# ext_pcb.net
KiCad netlist of a schematic drawn in EAGLE
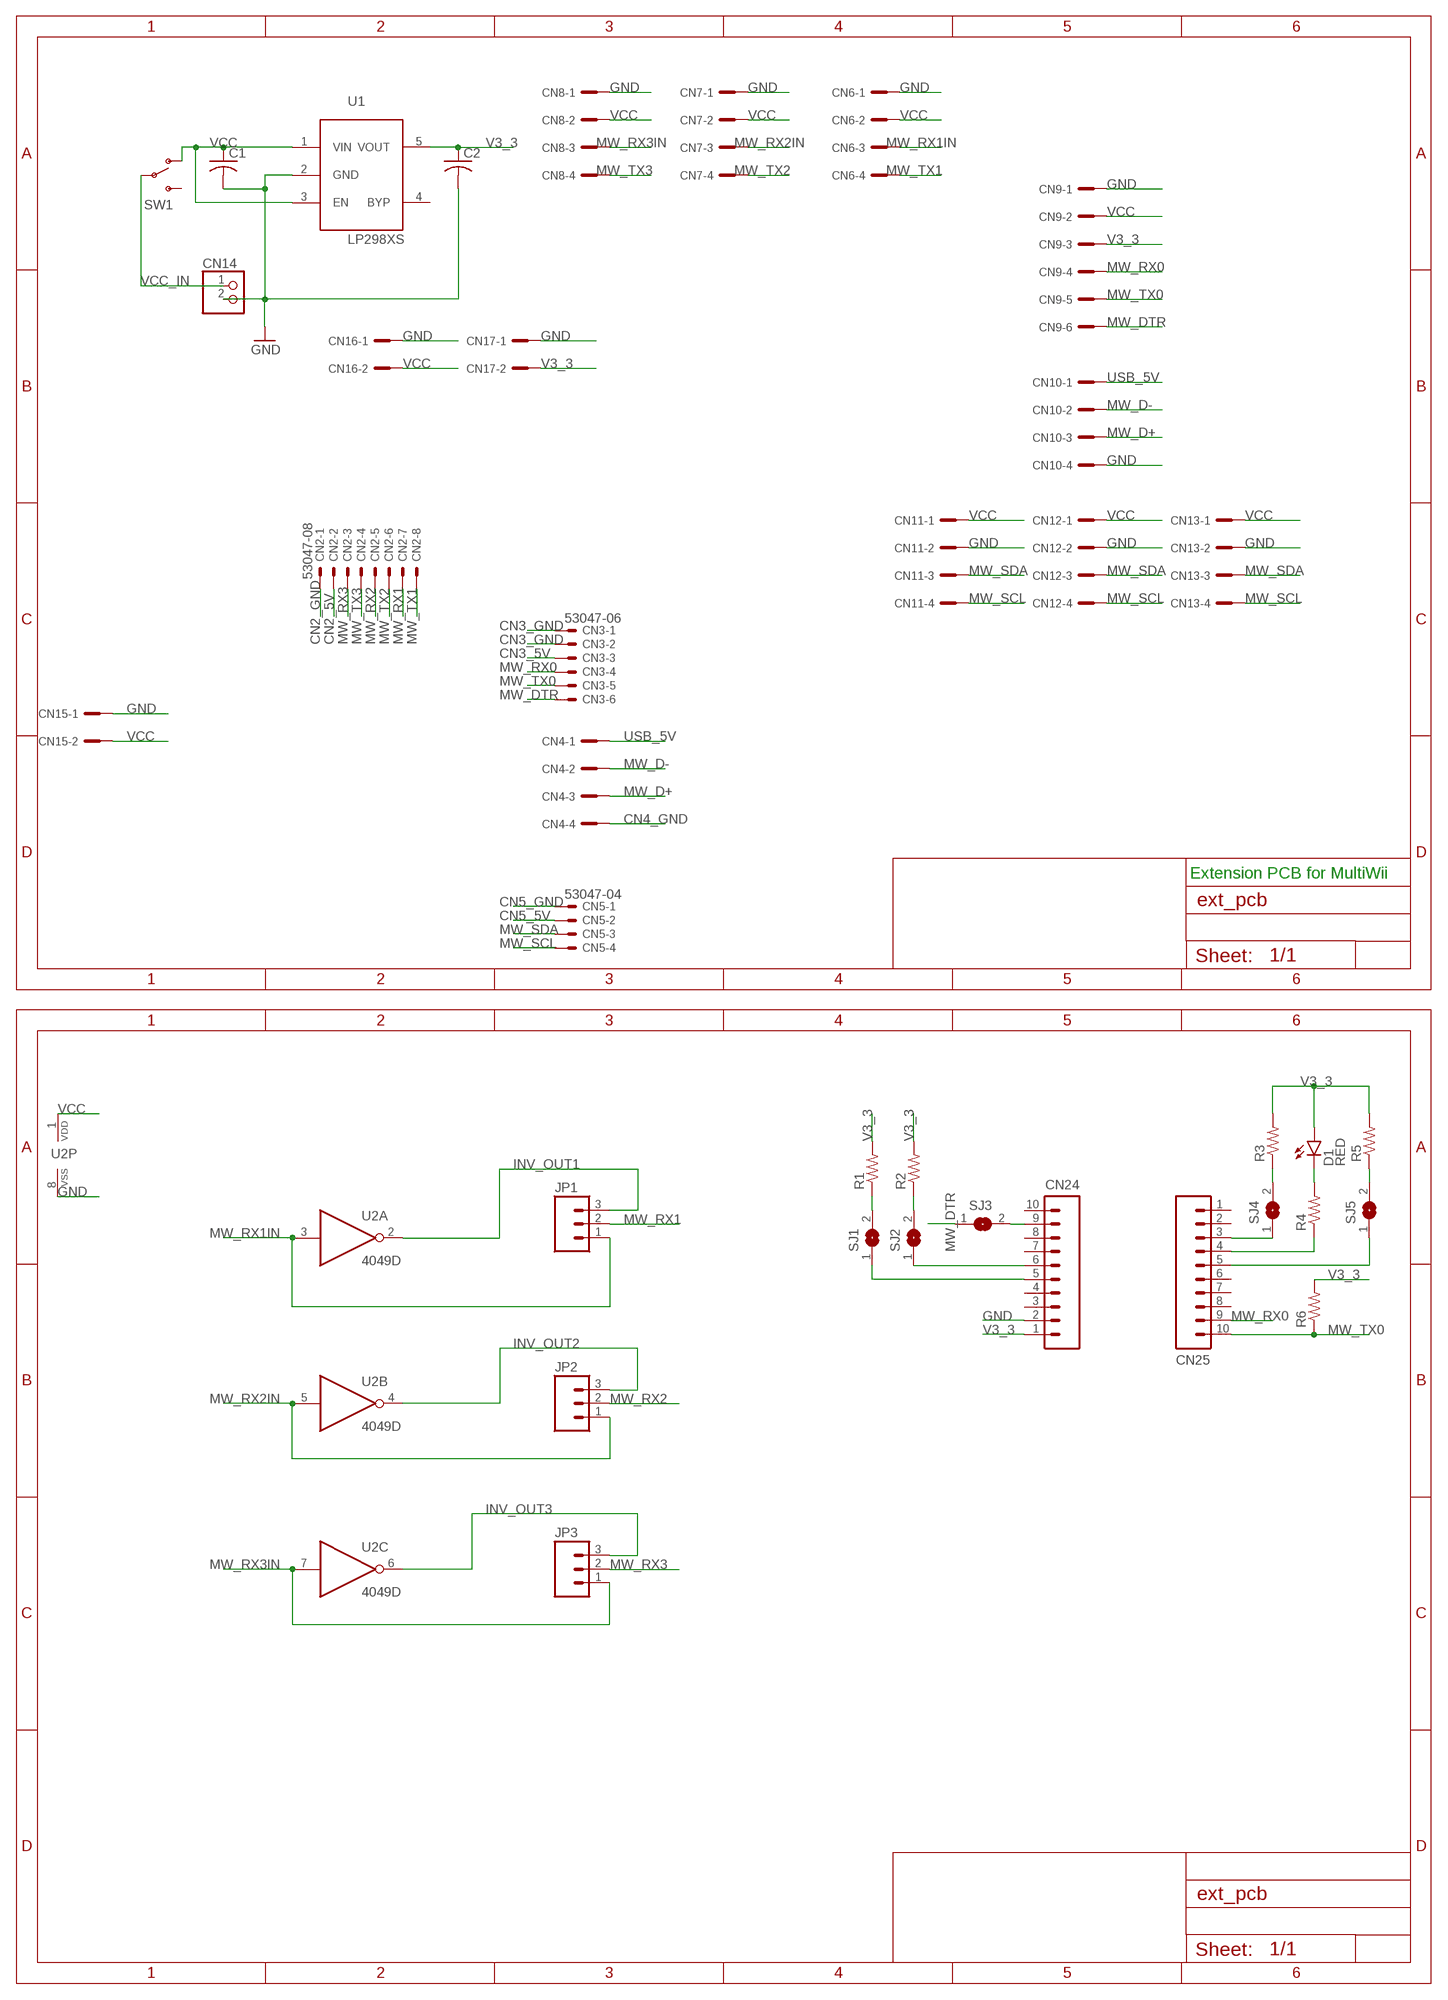
[diagram p0: schematic, sheet 1]

(export (version "E")
  (design (tool "Eeschema 10.0.6"))
  (components
    (comp (ref "C1")
      (value "C-USC0805")
      (footprint "eagle-import:C0805")
      (libsource (lib "eagle-import") (part "C-USC0805"))
    )
    (comp (ref "C2")
      (value "C-USC0805")
      (footprint "eagle-import:C0805")
      (libsource (lib "eagle-import") (part "C-USC0805"))
    )
    (comp (ref "CN2")
      (value "53047-08")
      (footprint "eagle-import:53047-08")
      (fields (field (name "MPN") "53047-0810"))
      (libsource (lib "eagle-import") (part "53?-08047"))
    )
    (comp (ref "CN3")
      (value "53047-06")
      (footprint "eagle-import:53047-06")
      (fields (field (name "MPN") "53047-0610-C"))
      (libsource (lib "eagle-import") (part "53?-06047"))
    )
    (comp (ref "CN4")
      (value "MCV_05/4-G-2,5V")
      (footprint "eagle-import:MCV4")
      (libsource (lib "eagle-import") (part "MCV_05/4-G-2,5V"))
    )
    (comp (ref "CN5")
      (value "53047-04")
      (footprint "eagle-import:53047-04")
      (fields (field (name "MF") "WALDOM/MOLEX") (field (name "MPN") "53047-0410"))
      (libsource (lib "eagle-import") (part "53?-04047"))
    )
    (comp (ref "CN6")
      (value "MCV_05/4-G-2,5V")
      (footprint "eagle-import:MCV4")
      (libsource (lib "eagle-import") (part "MCV_05/4-G-2,5V"))
    )
    (comp (ref "CN7")
      (value "MCV_05/4-G-2,5V")
      (footprint "eagle-import:MCV4")
      (libsource (lib "eagle-import") (part "MCV_05/4-G-2,5V"))
    )
    (comp (ref "CN8")
      (value "MCV_05/4-G-2,5V")
      (footprint "eagle-import:MCV4")
      (libsource (lib "eagle-import") (part "MCV_05/4-G-2,5V"))
    )
    (comp (ref "CN9")
      (value "MCV_05/6-G-2,5V")
      (footprint "eagle-import:MCV6")
      (libsource (lib "eagle-import") (part "MCV_05/6-G-2,5V"))
    )
    (comp (ref "CN10")
      (value "MCV_05/4-G-2,5V")
      (footprint "eagle-import:MCV4")
      (libsource (lib "eagle-import") (part "MCV_05/4-G-2,5V"))
    )
    (comp (ref "CN11")
      (value "MCV_05/4-G-2,5V")
      (footprint "eagle-import:MCV4")
      (libsource (lib "eagle-import") (part "MCV_05/4-G-2,5V"))
    )
    (comp (ref "CN12")
      (value "MCV_05/4-G-2,5V")
      (footprint "eagle-import:MCV4")
      (libsource (lib "eagle-import") (part "MCV_05/4-G-2,5V"))
    )
    (comp (ref "CN13")
      (value "MCV_05/4-G-2,5V")
      (footprint "eagle-import:MCV4")
      (libsource (lib "eagle-import") (part "MCV_05/4-G-2,5V"))
    )
    (comp (ref "CN14")
      (value "PINHD-1X2")
      (footprint "eagle-import:1X02")
      (libsource (lib "eagle-import") (part "PINHD-1X2"))
    )
    (comp (ref "CN15")
      (value "MCV_05/2-G-2,5V")
      (footprint "eagle-import:MCV2")
      (libsource (lib "eagle-import") (part "MCV_05/2-G-2,5V"))
    )
    (comp (ref "CN16")
      (value "MCV_05/2-G-2,5V")
      (footprint "eagle-import:MCV2")
      (libsource (lib "eagle-import") (part "MCV_05/2-G-2,5V"))
    )
    (comp (ref "CN17")
      (value "MCV_05/2-G-2,5V")
      (footprint "eagle-import:MCV2")
      (libsource (lib "eagle-import") (part "MCV_05/2-G-2,5V"))
    )
    (comp (ref "CN24")
      (value "M10SILK_FEMALE_PTH")
      (footprint "eagle-import:1X10")
      (libsource (lib "eagle-import") (part "M10SILK_FEMALE_PTH"))
    )
    (comp (ref "CN25")
      (value "M10SILK_FEMALE_PTH")
      (footprint "eagle-import:1X10")
      (libsource (lib "eagle-import") (part "M10SILK_FEMALE_PTH"))
    )
    (comp (ref "D1")
      (value "RED")
      (footprint "eagle-import:LED-1206")
      (libsource (lib "eagle-import") (part "LED-RED1206"))
    )
    (comp (ref "JP1")
      (value "M03PTH")
      (footprint "eagle-import:1X03")
      (libsource (lib "eagle-import") (part "M03PTH"))
    )
    (comp (ref "JP2")
      (value "M03PTH")
      (footprint "eagle-import:1X03")
      (libsource (lib "eagle-import") (part "M03PTH"))
    )
    (comp (ref "JP3")
      (value "M03PTH")
      (footprint "eagle-import:1X03")
      (libsource (lib "eagle-import") (part "M03PTH"))
    )
    (comp (ref "R1")
      (value "RESISTOR0805-RES")
      (footprint "eagle-import:0805")
      (libsource (lib "eagle-import") (part "RESISTOR0805-RES"))
    )
    (comp (ref "R2")
      (value "RESISTOR0805-RES")
      (footprint "eagle-import:0805")
      (libsource (lib "eagle-import") (part "RESISTOR0805-RES"))
    )
    (comp (ref "R3")
      (value "RESISTOR0805-RES")
      (footprint "eagle-import:0805")
      (libsource (lib "eagle-import") (part "RESISTOR0805-RES"))
    )
    (comp (ref "R4")
      (value "RESISTOR0805-RES")
      (footprint "eagle-import:0805")
      (libsource (lib "eagle-import") (part "RESISTOR0805-RES"))
    )
    (comp (ref "R5")
      (value "RESISTOR0805-RES")
      (footprint "eagle-import:0805")
      (libsource (lib "eagle-import") (part "RESISTOR0805-RES"))
    )
    (comp (ref "R6")
      (value "RESISTOR0805-RES")
      (footprint "eagle-import:0805")
      (libsource (lib "eagle-import") (part "RESISTOR0805-RES"))
    )
    (comp (ref "SJ1")
      (value "SJW")
      (footprint "eagle-import:SJW")
      (libsource (lib "eagle-import") (part "SJW"))
    )
    (comp (ref "SJ2")
      (value "SJW")
      (footprint "eagle-import:SJW")
      (libsource (lib "eagle-import") (part "SJW"))
    )
    (comp (ref "SJ3")
      (value "SJW")
      (footprint "eagle-import:SJW")
      (libsource (lib "eagle-import") (part "SJW"))
    )
    (comp (ref "SJ4")
      (value "SJW")
      (footprint "eagle-import:SJW")
      (libsource (lib "eagle-import") (part "SJW"))
    )
    (comp (ref "SJ5")
      (value "SJW")
      (footprint "eagle-import:SJW")
      (libsource (lib "eagle-import") (part "SJW"))
    )
    (comp (ref "SW1")
      (value "SWITCH-SPDTPTH")
      (footprint "eagle-import:SWITCH-SPDT")
      (libsource (lib "eagle-import") (part "SWITCH-SPDTPTH"))
    )
    (comp (ref "U1")
      (value "LP298XS")
      (footprint "eagle-import:SOT23-5L")
      (libsource (lib "eagle-import") (part "LP298XS"))
    )
    (comp (ref "U2")
      (value "4049D")
      (footprint "eagle-import:SO16")
      (libsource (lib "eagle-import") (part "4049D"))
    )
  )
  (nets
    (net (code "1") (name "/CN2_5V") (class "Default")
      (node (ref "CN2") (pin "2") (pinfunction "S_2") (pintype "passive"))
    )
    (net (code "2") (name "/CN2_GND") (class "Default")
      (node (ref "CN2") (pin "1") (pinfunction "S_1") (pintype "passive"))
    )
    (net (code "3") (name "/CN3_5V") (class "Default")
      (node (ref "CN3") (pin "3") (pinfunction "S_3") (pintype "passive"))
    )
    (net (code "4") (name "/CN3_GND") (class "Default")
      (node (ref "CN3") (pin "1") (pinfunction "S_1") (pintype "passive"))
      (node (ref "CN3") (pin "2") (pinfunction "S_2") (pintype "passive"))
    )
    (net (code "5") (name "/CN4_GND") (class "Default")
      (node (ref "CN4") (pin "4") (pinfunction "SK_4") (pintype "passive"))
    )
    (net (code "6") (name "/CN5_5V") (class "Default")
      (node (ref "CN5") (pin "2") (pinfunction "S_2") (pintype "passive"))
    )
    (net (code "7") (name "/CN5_GND") (class "Default")
      (node (ref "CN5") (pin "1") (pinfunction "S_1") (pintype "passive"))
    )
    (net (code "8") (name "/INV_OUT1") (class "Default")
      (node (ref "JP1") (pin "3") (pinfunction "3_3") (pintype "passive"))
      (node (ref "U2") (pin "2") (pinfunction "O_2") (pintype "output"))
    )
    (net (code "9") (name "/INV_OUT2") (class "Default")
      (node (ref "JP2") (pin "3") (pinfunction "3_3") (pintype "passive"))
      (node (ref "U2") (pin "4") (pinfunction "O_4") (pintype "output"))
    )
    (net (code "10") (name "/INV_OUT3") (class "Default")
      (node (ref "JP3") (pin "3") (pinfunction "3_3") (pintype "passive"))
      (node (ref "U2") (pin "6") (pinfunction "O_6") (pintype "output"))
    )
    (net (code "11") (name "/MW_D+") (class "Default")
      (node (ref "CN10") (pin "3") (pinfunction "SK_3") (pintype "passive"))
      (node (ref "CN4") (pin "3") (pinfunction "SK_3") (pintype "passive"))
    )
    (net (code "12") (name "/MW_D-") (class "Default")
      (node (ref "CN10") (pin "2") (pinfunction "SK_2") (pintype "passive"))
      (node (ref "CN4") (pin "2") (pinfunction "SK_2") (pintype "passive"))
    )
    (net (code "13") (name "/MW_DTR") (class "Default")
      (node (ref "CN3") (pin "6") (pinfunction "S_6") (pintype "passive"))
      (node (ref "CN9") (pin "6") (pinfunction "SK_6") (pintype "passive"))
      (node (ref "SJ3") (pin "1") (pinfunction "1_1") (pintype "passive"))
    )
    (net (code "14") (name "/MW_RX0") (class "Default")
      (node (ref "CN25") (pin "9") (pinfunction "9_9") (pintype "passive"))
      (node (ref "CN3") (pin "4") (pinfunction "S_4") (pintype "passive"))
      (node (ref "CN9") (pin "4") (pinfunction "SK_4") (pintype "passive"))
    )
    (net (code "15") (name "/MW_RX1") (class "Default")
      (node (ref "CN2") (pin "7") (pinfunction "S_7") (pintype "passive"))
      (node (ref "JP1") (pin "2") (pinfunction "2_2") (pintype "passive"))
    )
    (net (code "16") (name "/MW_RX1IN") (class "Default")
      (node (ref "CN6") (pin "3") (pinfunction "SK_3") (pintype "passive"))
      (node (ref "JP1") (pin "1") (pinfunction "1_1") (pintype "passive"))
      (node (ref "U2") (pin "3") (pinfunction "I_3") (pintype "input"))
    )
    (net (code "17") (name "/MW_RX2") (class "Default")
      (node (ref "CN2") (pin "5") (pinfunction "S_5") (pintype "passive"))
      (node (ref "JP2") (pin "2") (pinfunction "2_2") (pintype "passive"))
    )
    (net (code "18") (name "/MW_RX2IN") (class "Default")
      (node (ref "CN7") (pin "3") (pinfunction "SK_3") (pintype "passive"))
      (node (ref "JP2") (pin "1") (pinfunction "1_1") (pintype "passive"))
      (node (ref "U2") (pin "5") (pinfunction "I_5") (pintype "input"))
    )
    (net (code "19") (name "/MW_RX3") (class "Default")
      (node (ref "CN2") (pin "3") (pinfunction "S_3") (pintype "passive"))
      (node (ref "JP3") (pin "2") (pinfunction "2_2") (pintype "passive"))
    )
    (net (code "20") (name "/MW_RX3IN") (class "Default")
      (node (ref "CN8") (pin "3") (pinfunction "SK_3") (pintype "passive"))
      (node (ref "JP3") (pin "1") (pinfunction "1_1") (pintype "passive"))
      (node (ref "U2") (pin "7") (pinfunction "I_7") (pintype "input"))
    )
    (net (code "21") (name "/MW_SCL") (class "Default")
      (node (ref "CN11") (pin "4") (pinfunction "SK_4") (pintype "passive"))
      (node (ref "CN12") (pin "4") (pinfunction "SK_4") (pintype "passive"))
      (node (ref "CN13") (pin "4") (pinfunction "SK_4") (pintype "passive"))
      (node (ref "CN5") (pin "4") (pinfunction "S_4") (pintype "passive"))
    )
    (net (code "22") (name "/MW_SDA") (class "Default")
      (node (ref "CN11") (pin "3") (pinfunction "SK_3") (pintype "passive"))
      (node (ref "CN12") (pin "3") (pinfunction "SK_3") (pintype "passive"))
      (node (ref "CN13") (pin "3") (pinfunction "SK_3") (pintype "passive"))
      (node (ref "CN5") (pin "3") (pinfunction "S_3") (pintype "passive"))
    )
    (net (code "23") (name "/MW_TX0") (class "Default")
      (node (ref "CN25") (pin "10") (pinfunction "10_10") (pintype "passive"))
      (node (ref "CN3") (pin "5") (pinfunction "S_5") (pintype "passive"))
      (node (ref "CN9") (pin "5") (pinfunction "SK_5") (pintype "passive"))
      (node (ref "R6") (pin "1") (pinfunction "1_1") (pintype "passive"))
    )
    (net (code "24") (name "/MW_TX1") (class "Default")
      (node (ref "CN2") (pin "8") (pinfunction "S_8") (pintype "passive"))
      (node (ref "CN6") (pin "4") (pinfunction "SK_4") (pintype "passive"))
    )
    (net (code "25") (name "/MW_TX2") (class "Default")
      (node (ref "CN2") (pin "6") (pinfunction "S_6") (pintype "passive"))
      (node (ref "CN7") (pin "4") (pinfunction "SK_4") (pintype "passive"))
    )
    (net (code "26") (name "/MW_TX3") (class "Default")
      (node (ref "CN2") (pin "4") (pinfunction "S_4") (pintype "passive"))
      (node (ref "CN8") (pin "4") (pinfunction "SK_4") (pintype "passive"))
    )
    (net (code "27") (name "/USB_5V") (class "Default")
      (node (ref "CN10") (pin "1") (pinfunction "SK_1") (pintype "passive"))
      (node (ref "CN4") (pin "1") (pinfunction "SK_1") (pintype "passive"))
    )
    (net (code "28") (name "/V3_3") (class "Default")
      (node (ref "C2") (pin "1") (pinfunction "1_1") (pintype "passive"))
      (node (ref "CN17") (pin "2") (pinfunction "SK_2") (pintype "passive"))
      (node (ref "CN24") (pin "1") (pinfunction "1_1") (pintype "passive"))
      (node (ref "CN9") (pin "3") (pinfunction "SK_3") (pintype "passive"))
      (node (ref "D1") (pin "A") (pinfunction "A_A") (pintype "passive"))
      (node (ref "R1") (pin "2") (pinfunction "2_2") (pintype "passive"))
      (node (ref "R2") (pin "2") (pinfunction "2_2") (pintype "passive"))
      (node (ref "R3") (pin "2") (pinfunction "2_2") (pintype "passive"))
      (node (ref "R5") (pin "2") (pinfunction "2_2") (pintype "passive"))
      (node (ref "R6") (pin "2") (pinfunction "2_2") (pintype "passive"))
      (node (ref "U1") (pin "5") (pinfunction "VOUT_5") (pintype "bidirectional"))
    )
    (net (code "29") (name "/VCC") (class "Default")
      (node (ref "C1") (pin "1") (pinfunction "1_1") (pintype "passive"))
      (node (ref "CN11") (pin "1") (pinfunction "SK_1") (pintype "passive"))
      (node (ref "CN12") (pin "1") (pinfunction "SK_1") (pintype "passive"))
      (node (ref "CN13") (pin "1") (pinfunction "SK_1") (pintype "passive"))
      (node (ref "CN15") (pin "2") (pinfunction "SK_2") (pintype "passive"))
      (node (ref "CN16") (pin "2") (pinfunction "SK_2") (pintype "passive"))
      (node (ref "CN6") (pin "2") (pinfunction "SK_2") (pintype "passive"))
      (node (ref "CN7") (pin "2") (pinfunction "SK_2") (pintype "passive"))
      (node (ref "CN8") (pin "2") (pinfunction "SK_2") (pintype "passive"))
      (node (ref "CN9") (pin "2") (pinfunction "SK_2") (pintype "passive"))
      (node (ref "SW1") (pin "1") (pinfunction "O_1") (pintype "passive"))
      (node (ref "U1") (pin "1") (pinfunction "VIN_1") (pintype "bidirectional"))
      (node (ref "U1") (pin "3") (pinfunction "EN_3") (pintype "bidirectional"))
      (node (ref "U2") (pin "1") (pinfunction "VDD_1") (pintype "power_in"))
    )
    (net (code "30") (name "/VCC_IN") (class "Default")
      (node (ref "CN14") (pin "1") (pinfunction "1_1") (pintype "passive"))
      (node (ref "SW1") (pin "2") (pinfunction "P_2") (pintype "passive"))
    )
    (net (code "31") (name "GND") (class "Default")
      (node (ref "C1") (pin "2") (pinfunction "2_2") (pintype "passive"))
      (node (ref "C2") (pin "2") (pinfunction "2_2") (pintype "passive"))
      (node (ref "CN10") (pin "4") (pinfunction "SK_4") (pintype "passive"))
      (node (ref "CN11") (pin "2") (pinfunction "SK_2") (pintype "passive"))
      (node (ref "CN12") (pin "2") (pinfunction "SK_2") (pintype "passive"))
      (node (ref "CN13") (pin "2") (pinfunction "SK_2") (pintype "passive"))
      (node (ref "CN14") (pin "2") (pinfunction "2_2") (pintype "passive"))
      (node (ref "CN15") (pin "1") (pinfunction "SK_1") (pintype "passive"))
      (node (ref "CN16") (pin "1") (pinfunction "SK_1") (pintype "passive"))
      (node (ref "CN17") (pin "1") (pinfunction "SK_1") (pintype "passive"))
      (node (ref "CN24") (pin "2") (pinfunction "2_2") (pintype "passive"))
      (node (ref "CN6") (pin "1") (pinfunction "SK_1") (pintype "passive"))
      (node (ref "CN7") (pin "1") (pinfunction "SK_1") (pintype "passive"))
      (node (ref "CN8") (pin "1") (pinfunction "SK_1") (pintype "passive"))
      (node (ref "CN9") (pin "1") (pinfunction "SK_1") (pintype "passive"))
      (node (ref "U1") (pin "2") (pinfunction "GND_2") (pintype "bidirectional"))
      (node (ref "U2") (pin "8") (pinfunction "VSS_8") (pintype "power_in"))
    )
    (net (code "32") (name "Net-(CN24-Pad5)") (class "Default")
      (node (ref "CN24") (pin "5") (pinfunction "5_5") (pintype "passive"))
      (node (ref "SJ1") (pin "1") (pinfunction "1_1") (pintype "passive"))
    )
    (net (code "33") (name "Net-(CN24-Pad6)") (class "Default")
      (node (ref "CN24") (pin "6") (pinfunction "6_6") (pintype "passive"))
      (node (ref "SJ2") (pin "1") (pinfunction "1_1") (pintype "passive"))
    )
    (net (code "34") (name "Net-(CN24-Pad9)") (class "Default")
      (node (ref "CN24") (pin "9") (pinfunction "9_9") (pintype "passive"))
      (node (ref "SJ3") (pin "2") (pinfunction "2_2") (pintype "passive"))
    )
    (net (code "35") (name "Net-(CN25-Pad3)") (class "Default")
      (node (ref "CN25") (pin "3") (pinfunction "3_3") (pintype "passive"))
      (node (ref "SJ4") (pin "1") (pinfunction "1_1") (pintype "passive"))
    )
    (net (code "36") (name "Net-(CN25-Pad4)") (class "Default")
      (node (ref "CN25") (pin "4") (pinfunction "4_4") (pintype "passive"))
      (node (ref "R4") (pin "1") (pinfunction "1_1") (pintype "passive"))
    )
    (net (code "37") (name "Net-(CN25-Pad5)") (class "Default")
      (node (ref "CN25") (pin "5") (pinfunction "5_5") (pintype "passive"))
      (node (ref "SJ5") (pin "1") (pinfunction "1_1") (pintype "passive"))
    )
    (net (code "38") (name "Net-(D1-PadC)") (class "Default")
      (node (ref "D1") (pin "C") (pinfunction "C_C") (pintype "passive"))
      (node (ref "R4") (pin "2") (pinfunction "2_2") (pintype "passive"))
    )
    (net (code "39") (name "Net-(R1-Pad1)") (class "Default")
      (node (ref "R1") (pin "1") (pinfunction "1_1") (pintype "passive"))
      (node (ref "SJ1") (pin "2") (pinfunction "2_2") (pintype "passive"))
    )
    (net (code "40") (name "Net-(R2-Pad1)") (class "Default")
      (node (ref "R2") (pin "1") (pinfunction "1_1") (pintype "passive"))
      (node (ref "SJ2") (pin "2") (pinfunction "2_2") (pintype "passive"))
    )
    (net (code "41") (name "Net-(R3-Pad1)") (class "Default")
      (node (ref "R3") (pin "1") (pinfunction "1_1") (pintype "passive"))
      (node (ref "SJ4") (pin "2") (pinfunction "2_2") (pintype "passive"))
    )
    (net (code "42") (name "Net-(R5-Pad1)") (class "Default")
      (node (ref "R5") (pin "1") (pinfunction "1_1") (pintype "passive"))
      (node (ref "SJ5") (pin "2") (pinfunction "2_2") (pintype "passive"))
    )
    (net (code "43") (name "unconnected-(CN24-Pad3)") (class "Default")
      (node (ref "CN24") (pin "3") (pinfunction "3_3") (pintype "passive"))
    )
    (net (code "44") (name "unconnected-(CN24-Pad4)") (class "Default")
      (node (ref "CN24") (pin "4") (pinfunction "4_4") (pintype "passive"))
    )
    (net (code "45") (name "unconnected-(CN24-Pad7)") (class "Default")
      (node (ref "CN24") (pin "7") (pinfunction "7_7") (pintype "passive"))
    )
    (net (code "46") (name "unconnected-(CN24-Pad8)") (class "Default")
      (node (ref "CN24") (pin "8") (pinfunction "8_8") (pintype "passive"))
    )
    (net (code "47") (name "unconnected-(CN24-Pad10)") (class "Default")
      (node (ref "CN24") (pin "10") (pinfunction "10_10") (pintype "passive"))
    )
    (net (code "48") (name "unconnected-(CN25-Pad1)") (class "Default")
      (node (ref "CN25") (pin "1") (pinfunction "1_1") (pintype "passive"))
    )
    (net (code "49") (name "unconnected-(CN25-Pad2)") (class "Default")
      (node (ref "CN25") (pin "2") (pinfunction "2_2") (pintype "passive"))
    )
    (net (code "50") (name "unconnected-(CN25-Pad6)") (class "Default")
      (node (ref "CN25") (pin "6") (pinfunction "6_6") (pintype "passive"))
    )
    (net (code "51") (name "unconnected-(CN25-Pad7)") (class "Default")
      (node (ref "CN25") (pin "7") (pinfunction "7_7") (pintype "passive"))
    )
    (net (code "52") (name "unconnected-(CN25-Pad8)") (class "Default")
      (node (ref "CN25") (pin "8") (pinfunction "8_8") (pintype "passive"))
    )
    (net (code "53") (name "unconnected-(SW1-S-Pad3)") (class "Default")
      (node (ref "SW1") (pin "3") (pinfunction "S_3") (pintype "passive"))
    )
    (net (code "54") (name "unconnected-(U1-BYP-Pad4)") (class "Default")
      (node (ref "U1") (pin "4") (pinfunction "BYP_4") (pintype "bidirectional"))
    )
  )
)
